# EV-Board-Camera_V1_0.net
KiCad netlist of a schematic drawn in EAGLE
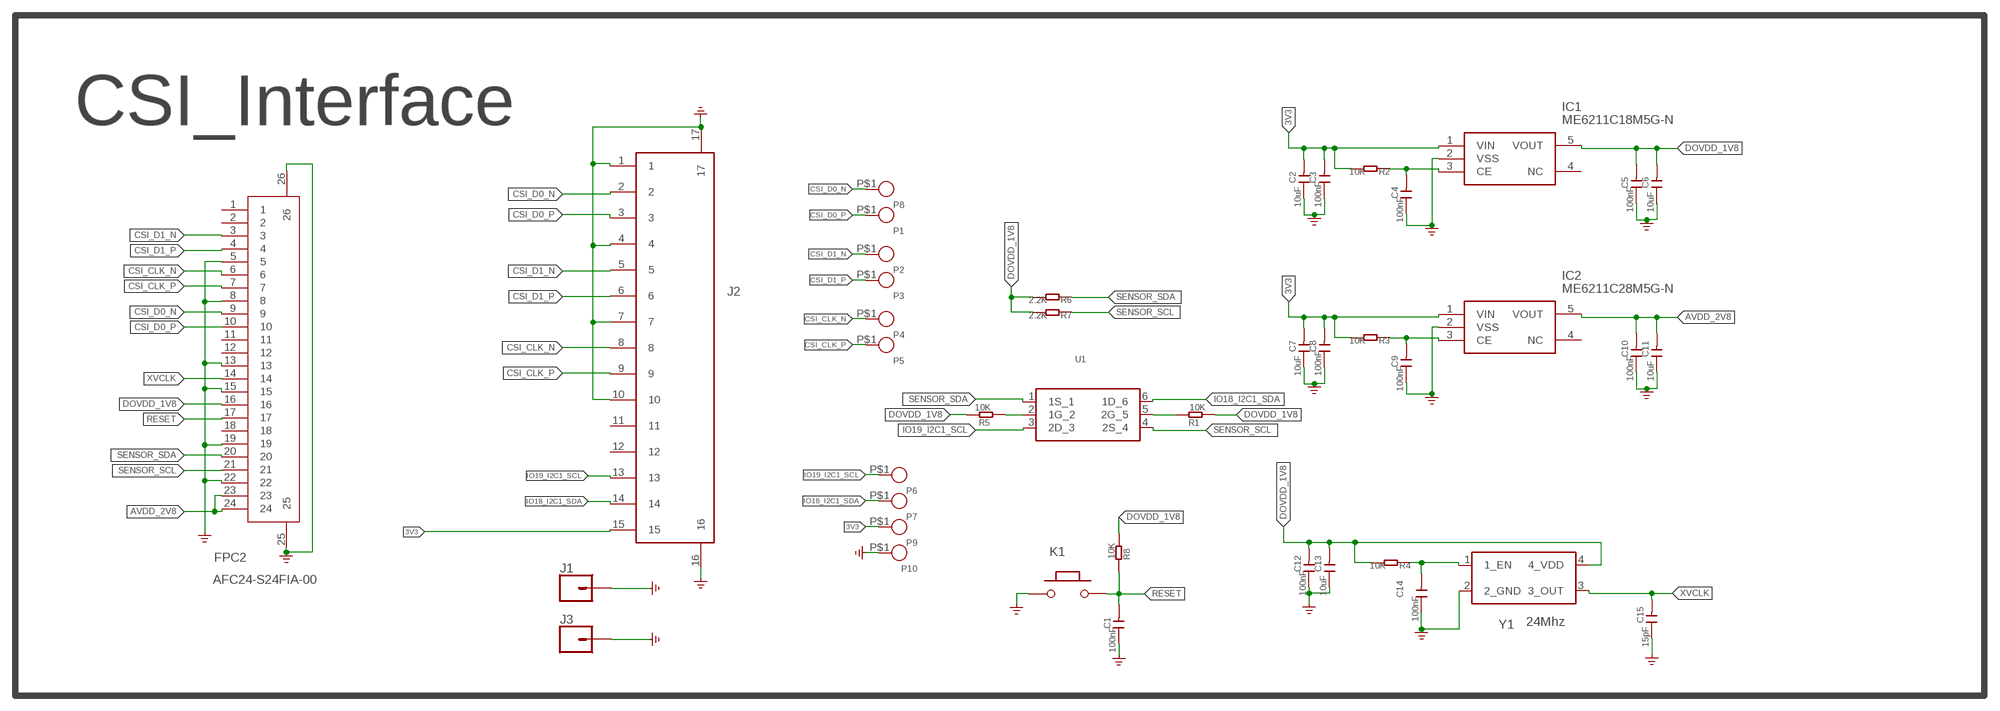
[diagram p0: schematic, sheet 1]

(export (version "E")
  (design (tool "Eeschema 10.0.6"))
  (components
    (comp (ref "C1")
      (value "100nF")
      (footprint "eagle-import:C0402")
      (libsource (lib "eagle-import") (part "CAPC0402-1"))
    )
    (comp (ref "C2")
      (value "10uF")
      (footprint "eagle-import:C0402")
      (libsource (lib "eagle-import") (part "CAPC0402-1"))
    )
    (comp (ref "C3")
      (value "100nF")
      (footprint "eagle-import:C0402")
      (libsource (lib "eagle-import") (part "CAPC0402-1"))
    )
    (comp (ref "C4")
      (value "100nF")
      (footprint "eagle-import:C0402")
      (libsource (lib "eagle-import") (part "CAPC0402-1"))
    )
    (comp (ref "C5")
      (value "100nF")
      (footprint "eagle-import:C0402")
      (libsource (lib "eagle-import") (part "CAPC0402-1"))
    )
    (comp (ref "C6")
      (value "10uF")
      (footprint "eagle-import:C0402")
      (libsource (lib "eagle-import") (part "CAPC0402-1"))
    )
    (comp (ref "C7")
      (value "10uF")
      (footprint "eagle-import:C0402")
      (libsource (lib "eagle-import") (part "CAPC0402-1"))
    )
    (comp (ref "C8")
      (value "100nF")
      (footprint "eagle-import:C0402")
      (libsource (lib "eagle-import") (part "CAPC0402-1"))
    )
    (comp (ref "C9")
      (value "100nF")
      (footprint "eagle-import:C0402")
      (libsource (lib "eagle-import") (part "CAPC0402-1"))
    )
    (comp (ref "C10")
      (value "100nF")
      (footprint "eagle-import:C0402")
      (libsource (lib "eagle-import") (part "CAPC0402-1"))
    )
    (comp (ref "C11")
      (value "10uF")
      (footprint "eagle-import:C0402")
      (libsource (lib "eagle-import") (part "CAPC0402-1"))
    )
    (comp (ref "C12")
      (value "100nF")
      (footprint "eagle-import:C0402")
      (libsource (lib "eagle-import") (part "CAPC0402-1"))
    )
    (comp (ref "C13")
      (value "10uF")
      (footprint "eagle-import:C0402")
      (libsource (lib "eagle-import") (part "CAPC0402-1"))
    )
    (comp (ref "C14")
      (value "100nF")
      (footprint "eagle-import:C0402")
      (libsource (lib "eagle-import") (part "CAPC0402-1"))
    )
    (comp (ref "C15")
      (value "15pF")
      (footprint "eagle-import:C0402")
      (libsource (lib "eagle-import") (part "CAPC0402-1"))
    )
    (comp (ref "FPC2")
      (value "AFC24-S24FIA-00")
      (footprint "eagle-import:FPC-SMD_P0.50-24P_QCHF-SM-H2.0")
      (libsource (lib "eagle-import") (part "AFC24-S24FIA-00"))
    )
    (comp (ref "IC1")
      (value "ME6211C18M5G-N")
      (footprint "eagle-import:SOT95P282X145-5N")
      (libsource (lib "eagle-import") (part "ME6211C18M5G-N"))
    )
    (comp (ref "IC2")
      (value "ME6211C28M5G-N")
      (footprint "eagle-import:SOT95P282X145-5N")
      (fields (field (name "MANUFACTURER_PART_NUMBER") "ME6211C18M5G-N"))
      (libsource (lib "eagle-import") (part "ME6211C18M5G-N"))
    )
    (comp (ref "J1")
      (value "CONN_01_3.1MM_SMD1X01_3.1MM_SMD")
      (footprint "eagle-import:1X01_2MM")
      (libsource (lib "eagle-import") (part "CONN_01_3.1MM_SMD1X01_3.1MM_SMD"))
    )
    (comp (ref "J2")
      (value "C262349_15P_1MM_下接_AFA07-S15FCC-00")
      (footprint "eagle-import:C262349_15P_1MM_下接_AFA07-S15FCC-00")
      (libsource (lib "eagle-import") (part "C262349_15P_1MM_下接_AFA07-S15FCC-00"))
    )
    (comp (ref "J3")
      (value "CONN_01_3.1MM_SMD1X01_3.1MM_SMD")
      (footprint "eagle-import:1X01_2MM")
      (libsource (lib "eagle-import") (part "CONN_01_3.1MM_SMD1X01_3.1MM_SMD"))
    )
    (comp (ref "K1")
      (value "BUTTON")
      (footprint "eagle-import:157SW")
      (libsource (lib "eagle-import") (part "PB157"))
    )
    (comp (ref "P1")
      (value "TEST_PADPAD-1.5MM")
      (footprint "eagle-import:TEST_PAD-1.5MM")
      (libsource (lib "eagle-import") (part "TEST_PADPAD-1.5MM"))
    )
    (comp (ref "P2")
      (value "TEST_PADPAD-1.5MM")
      (footprint "eagle-import:TEST_PAD-1.5MM")
      (libsource (lib "eagle-import") (part "TEST_PADPAD-1.5MM"))
    )
    (comp (ref "P3")
      (value "TEST_PADPAD-1.5MM")
      (footprint "eagle-import:TEST_PAD-1.5MM")
      (libsource (lib "eagle-import") (part "TEST_PADPAD-1.5MM"))
    )
    (comp (ref "P4")
      (value "TEST_PADPAD-1.5MM")
      (footprint "eagle-import:TEST_PAD-1.5MM")
      (libsource (lib "eagle-import") (part "TEST_PADPAD-1.5MM"))
    )
    (comp (ref "P5")
      (value "TEST_PADPAD-1.5MM")
      (footprint "eagle-import:TEST_PAD-1.5MM")
      (libsource (lib "eagle-import") (part "TEST_PADPAD-1.5MM"))
    )
    (comp (ref "P6")
      (value "TEST_PADPAD-1.5MM")
      (footprint "eagle-import:TEST_PAD-1.5MM")
      (libsource (lib "eagle-import") (part "TEST_PADPAD-1.5MM"))
    )
    (comp (ref "P7")
      (value "TEST_PADPAD-1.5MM")
      (footprint "eagle-import:TEST_PAD-1.5MM")
      (libsource (lib "eagle-import") (part "TEST_PADPAD-1.5MM"))
    )
    (comp (ref "P8")
      (value "TEST_PADPAD-1.5MM")
      (footprint "eagle-import:TEST_PAD-1.5MM")
      (libsource (lib "eagle-import") (part "TEST_PADPAD-1.5MM"))
    )
    (comp (ref "P9")
      (value "TEST_PADPAD-1.5MM")
      (footprint "eagle-import:TEST_PAD-1.5MM")
      (libsource (lib "eagle-import") (part "TEST_PADPAD-1.5MM"))
    )
    (comp (ref "P10")
      (value "TEST_PADPAD-1.5MM")
      (footprint "eagle-import:TEST_PAD-1.5MM")
      (libsource (lib "eagle-import") (part "TEST_PADPAD-1.5MM"))
    )
    (comp (ref "R1")
      (value "10K")
      (footprint "eagle-import:R0402")
      (libsource (lib "eagle-import") (part "RES-0402"))
    )
    (comp (ref "R2")
      (value "10K")
      (footprint "eagle-import:R0402")
      (libsource (lib "eagle-import") (part "RES-0402"))
    )
    (comp (ref "R3")
      (value "10K")
      (footprint "eagle-import:R0402")
      (libsource (lib "eagle-import") (part "RES-0402"))
    )
    (comp (ref "R4")
      (value "10K")
      (footprint "eagle-import:R0402")
      (libsource (lib "eagle-import") (part "RES-0402"))
    )
    (comp (ref "R5")
      (value "10K")
      (footprint "eagle-import:R0402")
      (libsource (lib "eagle-import") (part "RES-0402"))
    )
    (comp (ref "R6")
      (value "2.2K")
      (footprint "eagle-import:R0402")
      (libsource (lib "eagle-import") (part "RES-0402"))
    )
    (comp (ref "R7")
      (value "2.2K")
      (footprint "eagle-import:R0402")
      (libsource (lib "eagle-import") (part "RES-0402"))
    )
    (comp (ref "R8")
      (value "10K")
      (footprint "eagle-import:R0402")
      (libsource (lib "eagle-import") (part "RES-0402"))
    )
    (comp (ref "U1")
      (value "WST2006")
      (footprint "eagle-import:WST2006")
      (libsource (lib "eagle-import") (part "WST2006"))
    )
    (comp (ref "Y1")
      (value "24Mhz")
      (footprint "eagle-import:24MHZ_1631-24003-BTKEYA")
      (libsource (lib "eagle-import") (part "24MHZ"))
    )
  )
  (nets
    (net (code "1") (name "3V3") (class "Default")
      (node (ref "C2") (pin "2") (pinfunction "2_2") (pintype "passive"))
      (node (ref "C3") (pin "2") (pinfunction "2_2") (pintype "passive"))
      (node (ref "C7") (pin "2") (pinfunction "2_2") (pintype "passive"))
      (node (ref "C8") (pin "2") (pinfunction "2_2") (pintype "passive"))
      (node (ref "IC1") (pin "1") (pinfunction "VIN_1") (pintype "bidirectional"))
      (node (ref "IC2") (pin "1") (pinfunction "VIN_1") (pintype "bidirectional"))
      (node (ref "J2") (pin "15") (pinfunction "15_15") (pintype "bidirectional"))
      (node (ref "P9") (pin "P$1") (pinfunction "P$1_P$1") (pintype "bidirectional"))
      (node (ref "R2") (pin "2") (pinfunction "2_2") (pintype "passive"))
      (node (ref "R3") (pin "2") (pinfunction "2_2") (pintype "passive"))
    )
    (net (code "2") (name "AVDD_2V8") (class "Default")
      (node (ref "C10") (pin "2") (pinfunction "2_2") (pintype "passive"))
      (node (ref "C11") (pin "2") (pinfunction "2_2") (pintype "passive"))
      (node (ref "FPC2") (pin "23") (pinfunction "23_23") (pintype "bidirectional"))
      (node (ref "FPC2") (pin "24") (pinfunction "24_24") (pintype "bidirectional"))
      (node (ref "IC2") (pin "5") (pinfunction "VOUT_5") (pintype "bidirectional"))
    )
    (net (code "3") (name "CSI_CLK_N") (class "Default")
      (node (ref "FPC2") (pin "6") (pinfunction "6_6") (pintype "bidirectional"))
      (node (ref "J2") (pin "8") (pinfunction "8_8") (pintype "bidirectional"))
      (node (ref "P4") (pin "P$1") (pinfunction "P$1_P$1") (pintype "bidirectional"))
    )
    (net (code "4") (name "CSI_CLK_P") (class "Default")
      (node (ref "FPC2") (pin "7") (pinfunction "7_7") (pintype "bidirectional"))
      (node (ref "J2") (pin "9") (pinfunction "9_9") (pintype "bidirectional"))
      (node (ref "P5") (pin "P$1") (pinfunction "P$1_P$1") (pintype "bidirectional"))
    )
    (net (code "5") (name "CSI_D0_N") (class "Default")
      (node (ref "FPC2") (pin "9") (pinfunction "9_9") (pintype "bidirectional"))
      (node (ref "J2") (pin "2") (pinfunction "2_2") (pintype "bidirectional"))
      (node (ref "P8") (pin "P$1") (pinfunction "P$1_P$1") (pintype "bidirectional"))
    )
    (net (code "6") (name "CSI_D0_P") (class "Default")
      (node (ref "FPC2") (pin "10") (pinfunction "10_10") (pintype "bidirectional"))
      (node (ref "J2") (pin "3") (pinfunction "3_3") (pintype "bidirectional"))
      (node (ref "P1") (pin "P$1") (pinfunction "P$1_P$1") (pintype "bidirectional"))
    )
    (net (code "7") (name "CSI_D1_N") (class "Default")
      (node (ref "FPC2") (pin "3") (pinfunction "3_3") (pintype "bidirectional"))
      (node (ref "J2") (pin "5") (pinfunction "5_5") (pintype "bidirectional"))
      (node (ref "P2") (pin "P$1") (pinfunction "P$1_P$1") (pintype "bidirectional"))
    )
    (net (code "8") (name "CSI_D1_P") (class "Default")
      (node (ref "FPC2") (pin "4") (pinfunction "4_4") (pintype "bidirectional"))
      (node (ref "J2") (pin "6") (pinfunction "6_6") (pintype "bidirectional"))
      (node (ref "P3") (pin "P$1") (pinfunction "P$1_P$1") (pintype "bidirectional"))
    )
    (net (code "9") (name "DOVDD_1V8") (class "Default")
      (node (ref "C12") (pin "2") (pinfunction "2_2") (pintype "passive"))
      (node (ref "C13") (pin "2") (pinfunction "2_2") (pintype "passive"))
      (node (ref "C5") (pin "2") (pinfunction "2_2") (pintype "passive"))
      (node (ref "C6") (pin "2") (pinfunction "2_2") (pintype "passive"))
      (node (ref "FPC2") (pin "16") (pinfunction "16_16") (pintype "bidirectional"))
      (node (ref "IC1") (pin "5") (pinfunction "VOUT_5") (pintype "bidirectional"))
      (node (ref "R1") (pin "1") (pinfunction "1_1") (pintype "passive"))
      (node (ref "R4") (pin "2") (pinfunction "2_2") (pintype "passive"))
      (node (ref "R5") (pin "2") (pinfunction "2_2") (pintype "passive"))
      (node (ref "R6") (pin "2") (pinfunction "2_2") (pintype "passive"))
      (node (ref "R7") (pin "2") (pinfunction "2_2") (pintype "passive"))
      (node (ref "R8") (pin "1") (pinfunction "1_1") (pintype "passive"))
      (node (ref "Y1") (pin "4") (pinfunction "4_VDD_4") (pintype "bidirectional"))
    )
    (net (code "10") (name "IO18_I2C1_SDA") (class "Default")
      (node (ref "J2") (pin "14") (pinfunction "14_14") (pintype "bidirectional"))
      (node (ref "P7") (pin "P$1") (pinfunction "P$1_P$1") (pintype "bidirectional"))
      (node (ref "U1") (pin "6") (pinfunction "1D_6_6") (pintype "bidirectional"))
    )
    (net (code "11") (name "IO19_I2C1_SCL") (class "Default")
      (node (ref "J2") (pin "13") (pinfunction "13_13") (pintype "bidirectional"))
      (node (ref "P6") (pin "P$1") (pinfunction "P$1_P$1") (pintype "bidirectional"))
      (node (ref "U1") (pin "3") (pinfunction "2D_3_3") (pintype "bidirectional"))
    )
    (net (code "12") (name "Net-(IC1-CE)") (class "Default")
      (node (ref "C4") (pin "2") (pinfunction "2_2") (pintype "passive"))
      (node (ref "IC1") (pin "3") (pinfunction "CE_3") (pintype "bidirectional"))
      (node (ref "R2") (pin "1") (pinfunction "1_1") (pintype "passive"))
    )
    (net (code "13") (name "Net-(IC2-CE)") (class "Default")
      (node (ref "C9") (pin "2") (pinfunction "2_2") (pintype "passive"))
      (node (ref "IC2") (pin "3") (pinfunction "CE_3") (pintype "bidirectional"))
      (node (ref "R3") (pin "1") (pinfunction "1_1") (pintype "passive"))
    )
    (net (code "14") (name "Net-(U1-1G_2)") (class "Default")
      (node (ref "R5") (pin "1") (pinfunction "1_1") (pintype "passive"))
      (node (ref "U1") (pin "2") (pinfunction "1G_2_2") (pintype "bidirectional"))
    )
    (net (code "15") (name "Net-(U1-2G_5)") (class "Default")
      (node (ref "R1") (pin "2") (pinfunction "2_2") (pintype "passive"))
      (node (ref "U1") (pin "5") (pinfunction "2G_5_5") (pintype "bidirectional"))
    )
    (net (code "16") (name "Net-(Y1-1_EN)") (class "Default")
      (node (ref "C14") (pin "2") (pinfunction "2_2") (pintype "passive"))
      (node (ref "R4") (pin "1") (pinfunction "1_1") (pintype "passive"))
      (node (ref "Y1") (pin "1") (pinfunction "1_EN_1") (pintype "bidirectional"))
    )
    (net (code "17") (name "POWER_GND") (class "Default")
      (node (ref "C1") (pin "1") (pinfunction "1_1") (pintype "passive"))
      (node (ref "C10") (pin "1") (pinfunction "1_1") (pintype "passive"))
      (node (ref "C11") (pin "1") (pinfunction "1_1") (pintype "passive"))
      (node (ref "C12") (pin "1") (pinfunction "1_1") (pintype "passive"))
      (node (ref "C13") (pin "1") (pinfunction "1_1") (pintype "passive"))
      (node (ref "C14") (pin "1") (pinfunction "1_1") (pintype "passive"))
      (node (ref "C15") (pin "1") (pinfunction "1_1") (pintype "passive"))
      (node (ref "C2") (pin "1") (pinfunction "1_1") (pintype "passive"))
      (node (ref "C3") (pin "1") (pinfunction "1_1") (pintype "passive"))
      (node (ref "C4") (pin "1") (pinfunction "1_1") (pintype "passive"))
      (node (ref "C5") (pin "1") (pinfunction "1_1") (pintype "passive"))
      (node (ref "C6") (pin "1") (pinfunction "1_1") (pintype "passive"))
      (node (ref "C7") (pin "1") (pinfunction "1_1") (pintype "passive"))
      (node (ref "C8") (pin "1") (pinfunction "1_1") (pintype "passive"))
      (node (ref "C9") (pin "1") (pinfunction "1_1") (pintype "passive"))
      (node (ref "FPC2") (pin "13") (pinfunction "13_13") (pintype "bidirectional"))
      (node (ref "FPC2") (pin "15") (pinfunction "15_15") (pintype "bidirectional"))
      (node (ref "FPC2") (pin "19") (pinfunction "19_19") (pintype "bidirectional"))
      (node (ref "FPC2") (pin "22") (pinfunction "22_22") (pintype "bidirectional"))
      (node (ref "FPC2") (pin "25") (pinfunction "25_25") (pintype "bidirectional"))
      (node (ref "FPC2") (pin "26") (pinfunction "26_26") (pintype "bidirectional"))
      (node (ref "FPC2") (pin "5") (pinfunction "5_5") (pintype "bidirectional"))
      (node (ref "FPC2") (pin "8") (pinfunction "8_8") (pintype "bidirectional"))
      (node (ref "IC1") (pin "2") (pinfunction "VSS_2") (pintype "bidirectional"))
      (node (ref "IC2") (pin "2") (pinfunction "VSS_2") (pintype "bidirectional"))
      (node (ref "J1") (pin "1") (pinfunction "1_1") (pintype "passive"))
      (node (ref "J2") (pin "1") (pinfunction "1_1") (pintype "bidirectional"))
      (node (ref "J2") (pin "10") (pinfunction "10_10") (pintype "bidirectional"))
      (node (ref "J2") (pin "16") (pinfunction "16_16") (pintype "bidirectional"))
      (node (ref "J2") (pin "17") (pinfunction "17_17") (pintype "bidirectional"))
      (node (ref "J2") (pin "4") (pinfunction "4_4") (pintype "bidirectional"))
      (node (ref "J2") (pin "7") (pinfunction "7_7") (pintype "bidirectional"))
      (node (ref "J3") (pin "1") (pinfunction "1_1") (pintype "passive"))
      (node (ref "K1") (pin "1") (pinfunction "1_1") (pintype "passive"))
      (node (ref "P10") (pin "P$1") (pinfunction "P$1_P$1") (pintype "bidirectional"))
      (node (ref "Y1") (pin "2") (pinfunction "2_GND_2") (pintype "bidirectional"))
    )
    (net (code "18") (name "RESET") (class "Default")
      (node (ref "C1") (pin "2") (pinfunction "2_2") (pintype "passive"))
      (node (ref "FPC2") (pin "17") (pinfunction "17_17") (pintype "bidirectional"))
      (node (ref "K1") (pin "2") (pinfunction "2_2") (pintype "passive"))
      (node (ref "R8") (pin "2") (pinfunction "2_2") (pintype "passive"))
    )
    (net (code "19") (name "SENSOR_SCL") (class "Default")
      (node (ref "FPC2") (pin "21") (pinfunction "21_21") (pintype "bidirectional"))
      (node (ref "R7") (pin "1") (pinfunction "1_1") (pintype "passive"))
      (node (ref "U1") (pin "4") (pinfunction "2S_4_4") (pintype "bidirectional"))
    )
    (net (code "20") (name "SENSOR_SDA") (class "Default")
      (node (ref "FPC2") (pin "20") (pinfunction "20_20") (pintype "bidirectional"))
      (node (ref "R6") (pin "1") (pinfunction "1_1") (pintype "passive"))
      (node (ref "U1") (pin "1") (pinfunction "1S_1_1") (pintype "bidirectional"))
    )
    (net (code "21") (name "XVCLK") (class "Default")
      (node (ref "C15") (pin "2") (pinfunction "2_2") (pintype "passive"))
      (node (ref "FPC2") (pin "14") (pinfunction "14_14") (pintype "bidirectional"))
      (node (ref "Y1") (pin "3") (pinfunction "3_OUT_3") (pintype "bidirectional"))
    )
    (net (code "22") (name "unconnected-(FPC2-Pad1)") (class "Default")
      (node (ref "FPC2") (pin "1") (pinfunction "1_1") (pintype "bidirectional"))
    )
    (net (code "23") (name "unconnected-(FPC2-Pad2)") (class "Default")
      (node (ref "FPC2") (pin "2") (pinfunction "2_2") (pintype "bidirectional"))
    )
    (net (code "24") (name "unconnected-(FPC2-Pad11)") (class "Default")
      (node (ref "FPC2") (pin "11") (pinfunction "11_11") (pintype "bidirectional"))
    )
    (net (code "25") (name "unconnected-(FPC2-Pad12)") (class "Default")
      (node (ref "FPC2") (pin "12") (pinfunction "12_12") (pintype "bidirectional"))
    )
    (net (code "26") (name "unconnected-(FPC2-Pad18)") (class "Default")
      (node (ref "FPC2") (pin "18") (pinfunction "18_18") (pintype "bidirectional"))
    )
    (net (code "27") (name "unconnected-(IC1-NC-Pad4)") (class "Default")
      (node (ref "IC1") (pin "4") (pinfunction "NC_4") (pintype "no_connect"))
    )
    (net (code "28") (name "unconnected-(IC2-NC-Pad4)") (class "Default")
      (node (ref "IC2") (pin "4") (pinfunction "NC_4") (pintype "no_connect"))
    )
    (net (code "29") (name "unconnected-(J2-Pad11)") (class "Default")
      (node (ref "J2") (pin "11") (pinfunction "11_11") (pintype "bidirectional"))
    )
    (net (code "30") (name "unconnected-(J2-Pad12)") (class "Default")
      (node (ref "J2") (pin "12") (pinfunction "12_12") (pintype "bidirectional"))
    )
  )
)
